# blink1mk3_micro1a.net
KiCad netlist of a schematic drawn in EAGLE
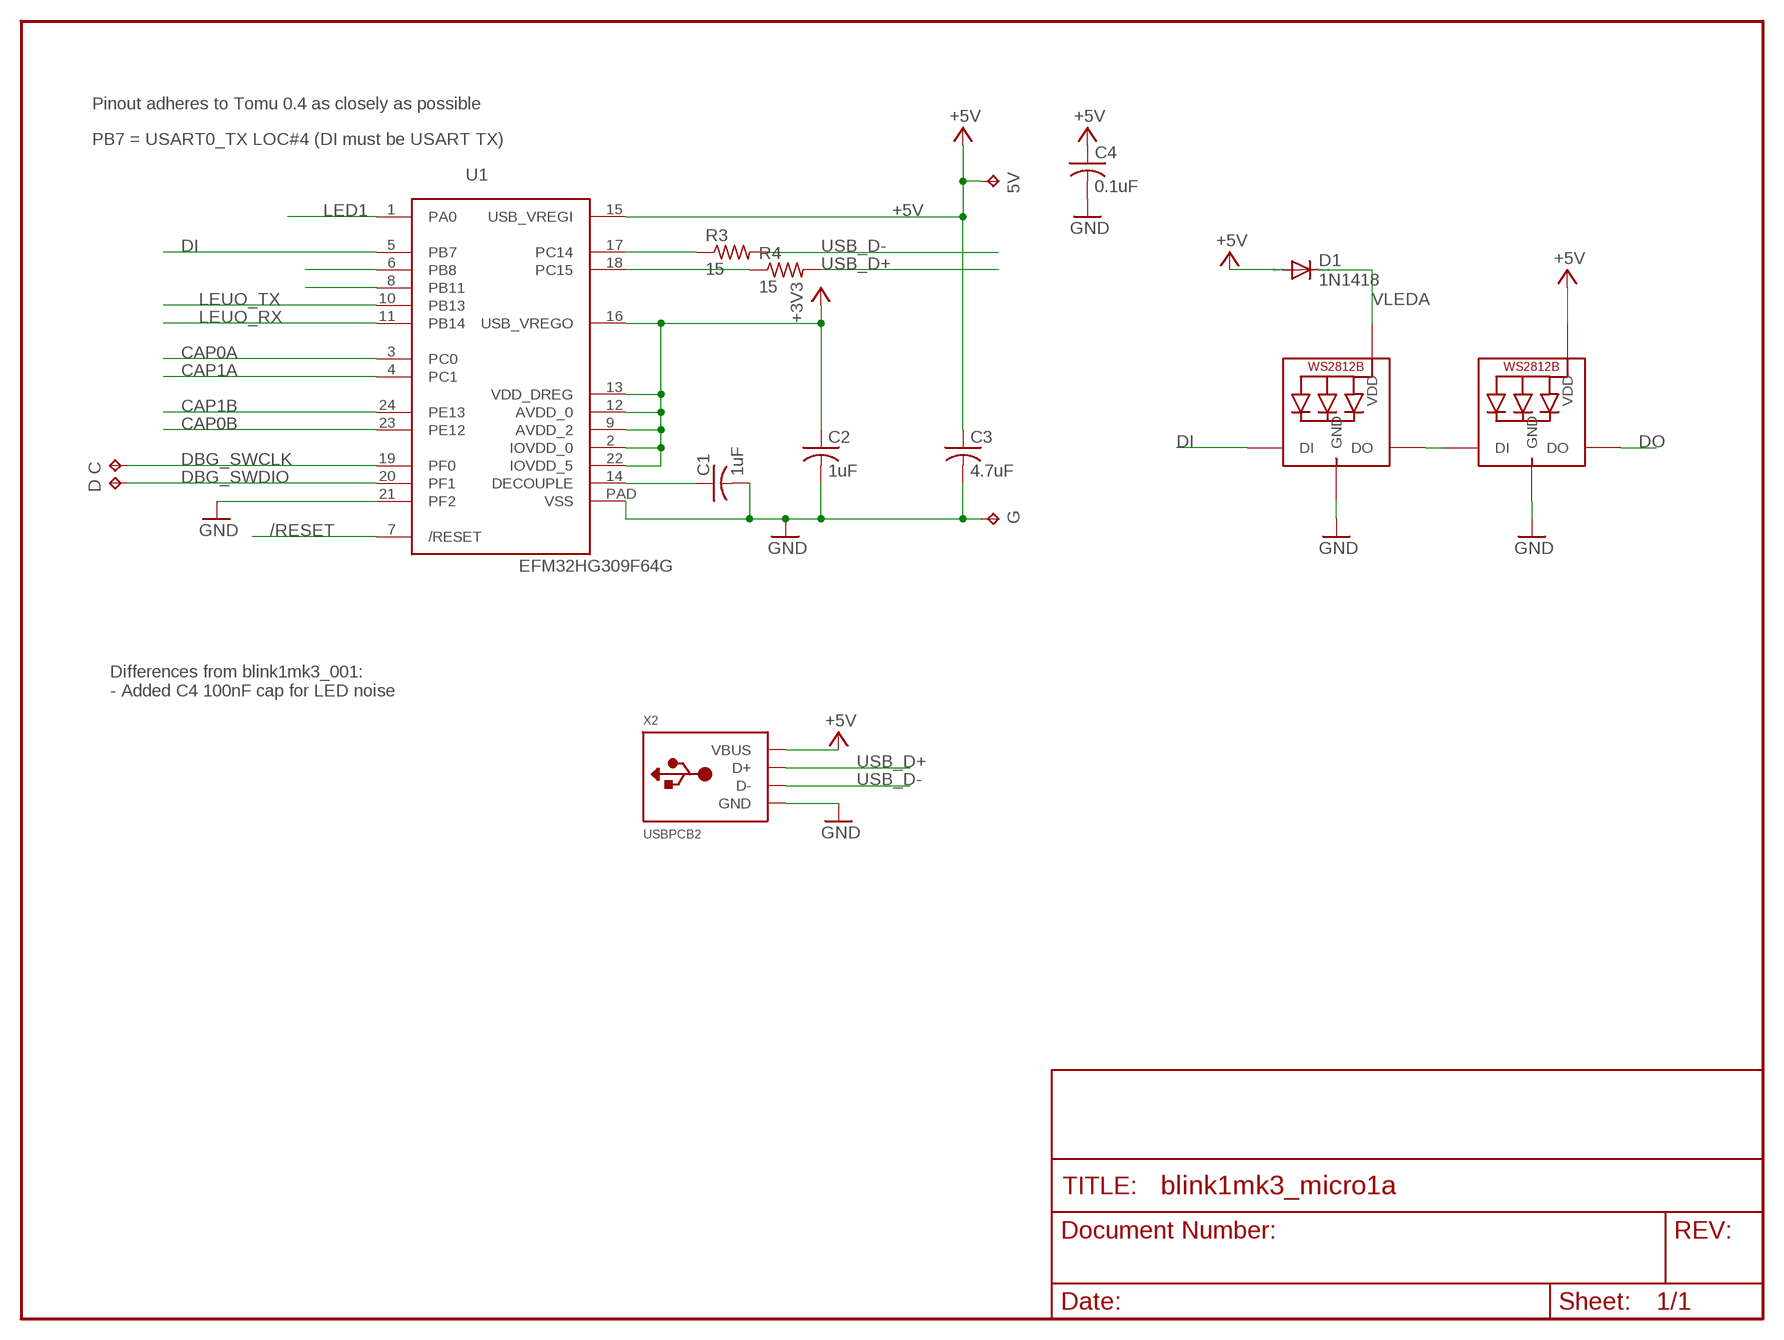
[diagram p0: schematic, sheet 1]

(export (version "E")
  (design (tool "Eeschema 10.0.6"))
  (components
    (comp (ref "5V")
      (value "TPTP10R")
      (footprint "eagle-import:TP10R")
      (libsource (lib "eagle-import") (part "TPTP10R"))
    )
    (comp (ref "C")
      (value "TPTP10R")
      (footprint "eagle-import:TP10R")
      (libsource (lib "eagle-import") (part "TPTP10R"))
    )
    (comp (ref "C1")
      (value "1uF")
      (footprint "eagle-import:C0402")
      (libsource (lib "eagle-import") (part "C-USC0402"))
    )
    (comp (ref "C2")
      (value "1uF")
      (footprint "eagle-import:C0402")
      (libsource (lib "eagle-import") (part "C-USC0402"))
    )
    (comp (ref "C3")
      (value "4.7uF")
      (footprint "eagle-import:C0402")
      (libsource (lib "eagle-import") (part "C-USC0402"))
    )
    (comp (ref "C4")
      (value "0.1uF")
      (footprint "eagle-import:C0402")
      (libsource (lib "eagle-import") (part "C-USC0402"))
    )
    (comp (ref "D")
      (value "TPTP10R")
      (footprint "eagle-import:TP10R")
      (libsource (lib "eagle-import") (part "TPTP10R"))
    )
    (comp (ref "D1")
      (value "1N1418")
      (footprint "eagle-import:SOD523")
      (libsource (lib "eagle-import") (part "DIODE-SOD523"))
    )
    (comp (ref "G")
      (value "TPTP10SQ")
      (footprint "eagle-import:TP10SQ")
      (libsource (lib "eagle-import") (part "TPTP10SQ"))
    )
    (comp (ref "LED1")
      (value "WS2812B4020SIDE")
      (footprint "eagle-import:SK6812-SIDE")
      (libsource (lib "eagle-import") (part "WS2812B4020SIDE"))
    )
    (comp (ref "LED2")
      (value "WS2812B4020SIDE")
      (footprint "eagle-import:SK6812-SIDE")
      (libsource (lib "eagle-import") (part "WS2812B4020SIDE"))
    )
    (comp (ref "R3")
      (value "15")
      (footprint "eagle-import:R0402")
      (libsource (lib "eagle-import") (part "R-US_R0402"))
    )
    (comp (ref "R4")
      (value "15")
      (footprint "eagle-import:R0402")
      (libsource (lib "eagle-import") (part "R-US_R0402"))
    )
    (comp (ref "U1")
      (value "EFM32HG309F64G")
      (footprint "eagle-import:QFN24PAD")
      (libsource (lib "eagle-import") (part "EFM32HG309F64G"))
    )
    (comp (ref "X2")
      (value "USBPCB2")
      (footprint "eagle-import:USB-A-PCB-2")
      (libsource (lib "eagle-import") (part "USBPCB2"))
    )
  )
  (nets
    (net (code "1") (name "+3V3") (class "Default")
      (node (ref "C2") (pin "1") (pinfunction "1_1") (pintype "passive"))
      (node (ref "U1") (pin "12") (pinfunction "AVDD_0_12") (pintype "bidirectional"))
      (node (ref "U1") (pin "13") (pinfunction "VDD_DREG_13") (pintype "bidirectional"))
      (node (ref "U1") (pin "16") (pinfunction "USB_VREGO_16") (pintype "bidirectional"))
      (node (ref "U1") (pin "2") (pinfunction "IOVDD_0_2") (pintype "bidirectional"))
      (node (ref "U1") (pin "22") (pinfunction "IOVDD_5_22") (pintype "bidirectional"))
      (node (ref "U1") (pin "9") (pinfunction "AVDD_2_9") (pintype "bidirectional"))
    )
    (net (code "2") (name "+5V") (class "Default")
      (node (ref "5V") (pin "TP") (pinfunction "TP_TP") (pintype "input"))
      (node (ref "C3") (pin "1") (pinfunction "1_1") (pintype "passive"))
      (node (ref "C4") (pin "1") (pinfunction "1_1") (pintype "passive"))
      (node (ref "D1") (pin "A") (pinfunction "A_A") (pintype "passive"))
      (node (ref "LED2") (pin "1-VDD") (pinfunction "VDD_1-VDD") (pintype "power_in"))
      (node (ref "U1") (pin "15") (pinfunction "USB_VREGI_15") (pintype "bidirectional"))
      (node (ref "X2") (pin "5V") (pinfunction "VBUS_5V") (pintype "power_in"))
    )
    (net (code "3") (name "/CAP0A") (class "Default")
      (node (ref "U1") (pin "3") (pinfunction "PC0_3") (pintype "bidirectional"))
    )
    (net (code "4") (name "/CAP0B") (class "Default")
      (node (ref "U1") (pin "23") (pinfunction "PE12_23") (pintype "bidirectional"))
    )
    (net (code "5") (name "/CAP1A") (class "Default")
      (node (ref "U1") (pin "4") (pinfunction "PC1_4") (pintype "bidirectional"))
    )
    (net (code "6") (name "/CAP1B") (class "Default")
      (node (ref "U1") (pin "24") (pinfunction "PE13_24") (pintype "bidirectional"))
    )
    (net (code "7") (name "/DBG_SWCLK") (class "Default")
      (node (ref "C") (pin "TP") (pinfunction "TP_TP") (pintype "input"))
      (node (ref "U1") (pin "19") (pinfunction "PF0_19") (pintype "bidirectional"))
    )
    (net (code "8") (name "/DBG_SWDIO") (class "Default")
      (node (ref "D") (pin "TP") (pinfunction "TP_TP") (pintype "input"))
      (node (ref "U1") (pin "20") (pinfunction "PF1_20") (pintype "bidirectional"))
    )
    (net (code "9") (name "/DI") (class "Default")
      (node (ref "LED1") (pin "4-DIN") (pinfunction "DI_4-DIN") (pintype "input"))
      (node (ref "U1") (pin "5") (pinfunction "PB7_5") (pintype "bidirectional"))
    )
    (net (code "10") (name "/DO") (class "Default")
      (node (ref "LED2") (pin "2-DOUT") (pinfunction "DO_2-DOUT") (pintype "output"))
    )
    (net (code "11") (name "/LED1") (class "Default")
      (node (ref "U1") (pin "1") (pinfunction "PA0_1") (pintype "bidirectional"))
    )
    (net (code "12") (name "/LEUO_RX") (class "Default")
      (node (ref "U1") (pin "11") (pinfunction "PB14_11") (pintype "bidirectional"))
    )
    (net (code "13") (name "/LEUO_TX") (class "Default")
      (node (ref "U1") (pin "10") (pinfunction "PB13_10") (pintype "bidirectional"))
    )
    (net (code "14") (name "/USB_D+") (class "Default")
      (node (ref "R4") (pin "2") (pinfunction "2_2") (pintype "passive"))
      (node (ref "X2") (pin "USB_P") (pinfunction "D+_USB_P") (pintype "bidirectional"))
    )
    (net (code "15") (name "/USB_D-") (class "Default")
      (node (ref "R3") (pin "2") (pinfunction "2_2") (pintype "passive"))
      (node (ref "X2") (pin "USB_M") (pinfunction "D-_USB_M") (pintype "bidirectional"))
    )
    (net (code "16") (name "/VLEDA") (class "Default")
      (node (ref "D1") (pin "C") (pinfunction "C_C") (pintype "passive"))
      (node (ref "LED1") (pin "1-VDD") (pinfunction "VDD_1-VDD") (pintype "power_in"))
    )
    (net (code "17") (name "/{slash}RESET") (class "Default")
      (node (ref "U1") (pin "7") (pinfunction "/RESET_7") (pintype "bidirectional"))
    )
    (net (code "18") (name "GND") (class "Default")
      (node (ref "C1") (pin "2") (pinfunction "2_2") (pintype "passive"))
      (node (ref "C2") (pin "2") (pinfunction "2_2") (pintype "passive"))
      (node (ref "C3") (pin "2") (pinfunction "2_2") (pintype "passive"))
      (node (ref "C4") (pin "2") (pinfunction "2_2") (pintype "passive"))
      (node (ref "G") (pin "TP") (pinfunction "TP_TP") (pintype "input"))
      (node (ref "LED1") (pin "3-GND") (pinfunction "GND_3-GND") (pintype "power_in"))
      (node (ref "LED2") (pin "3-GND") (pinfunction "GND_3-GND") (pintype "power_in"))
      (node (ref "U1") (pin "21") (pinfunction "PF2_21") (pintype "bidirectional"))
      (node (ref "U1") (pin "PAD") (pinfunction "VSS_PAD") (pintype "bidirectional"))
      (node (ref "X2") (pin "GND") (pinfunction "GND_GND") (pintype "power_in"))
    )
    (net (code "19") (name "Net-(LED1-DO)") (class "Default")
      (node (ref "LED1") (pin "2-DOUT") (pinfunction "DO_2-DOUT") (pintype "output"))
      (node (ref "LED2") (pin "4-DIN") (pinfunction "DI_4-DIN") (pintype "input"))
    )
    (net (code "20") (name "Net-(U1-DECOUPLE)") (class "Default")
      (node (ref "C1") (pin "1") (pinfunction "1_1") (pintype "passive"))
      (node (ref "U1") (pin "14") (pinfunction "DECOUPLE_14") (pintype "bidirectional"))
    )
    (net (code "21") (name "Net-(U1-PC14)") (class "Default")
      (node (ref "R3") (pin "1") (pinfunction "1_1") (pintype "passive"))
      (node (ref "U1") (pin "17") (pinfunction "PC14_17") (pintype "bidirectional"))
    )
    (net (code "22") (name "Net-(U1-PC15)") (class "Default")
      (node (ref "R4") (pin "1") (pinfunction "1_1") (pintype "passive"))
      (node (ref "U1") (pin "18") (pinfunction "PC15_18") (pintype "bidirectional"))
    )
    (net (code "23") (name "unconnected-(U1-PB8-Pad6)") (class "Default")
      (node (ref "U1") (pin "6") (pinfunction "PB8_6") (pintype "bidirectional"))
    )
    (net (code "24") (name "unconnected-(U1-PB11-Pad8)") (class "Default")
      (node (ref "U1") (pin "8") (pinfunction "PB11_8") (pintype "bidirectional"))
    )
  )
)
